# MSGP.net
KiCad netlist of a schematic drawn in EAGLE
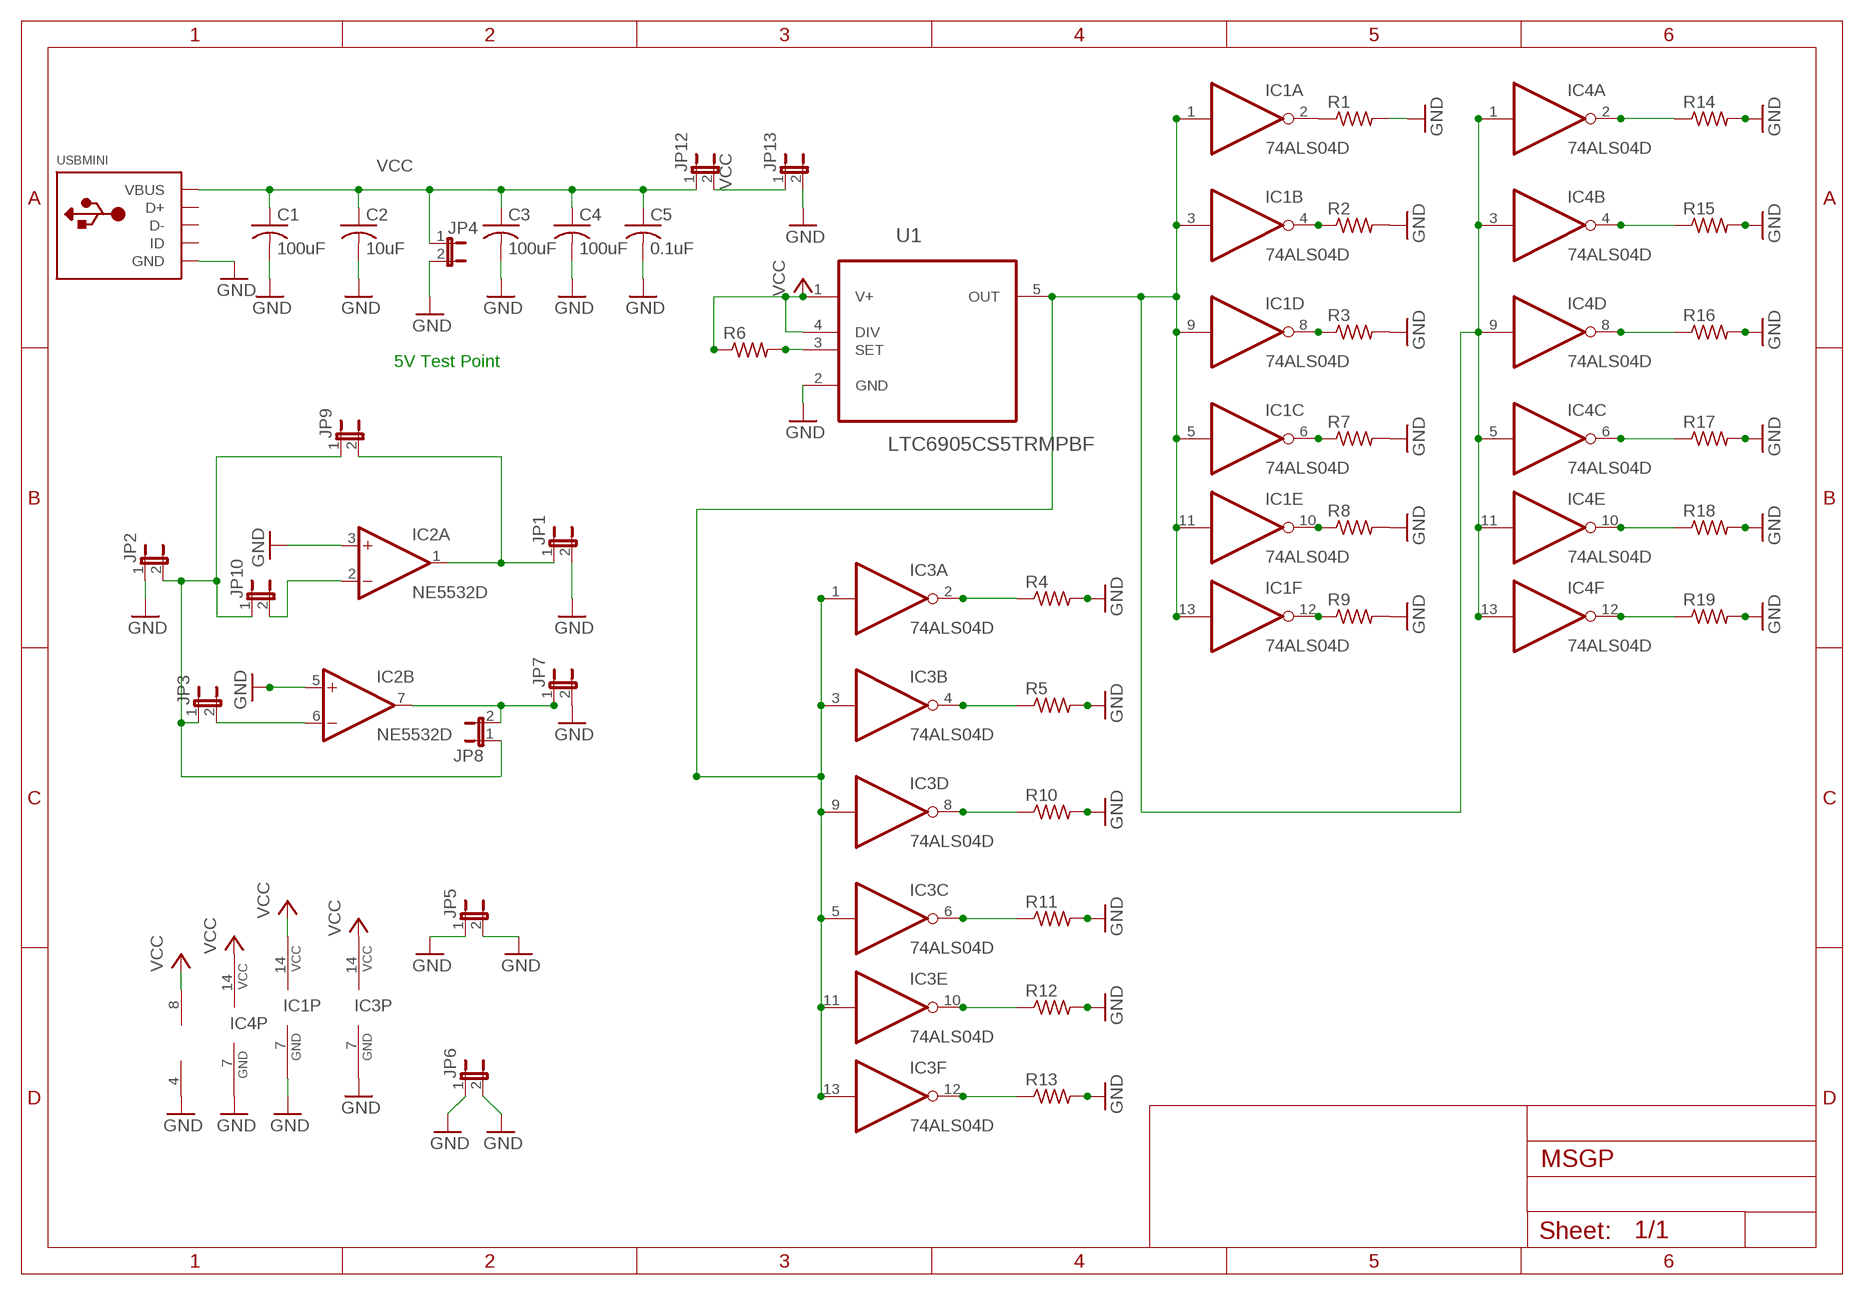
[diagram p0: schematic, sheet 1]

(export (version "E")
  (design (tool "Eeschema 10.0.6"))
  (components
    (comp (ref "C1")
      (value "100uF")
      (footprint "eagle-import:C1206K")
      (libsource (lib "eagle-import") (part "C-USC1206K"))
    )
    (comp (ref "C2")
      (value "10uF")
      (footprint "eagle-import:C1206K")
      (libsource (lib "eagle-import") (part "C-USC1206K"))
    )
    (comp (ref "C3")
      (value "100uF")
      (footprint "eagle-import:C1206K")
      (libsource (lib "eagle-import") (part "C-USC1206K"))
    )
    (comp (ref "C4")
      (value "100uF")
      (footprint "eagle-import:C1206K")
      (libsource (lib "eagle-import") (part "C-USC1206K"))
    )
    (comp (ref "C5")
      (value "0.1uF")
      (footprint "eagle-import:C1206K")
      (libsource (lib "eagle-import") (part "C-USC1206K"))
    )
    (comp (ref "IC1")
      (value "74ALS04D")
      (footprint "eagle-import:SO14")
      (libsource (lib "eagle-import") (part "7404DALS"))
    )
    (comp (ref "IC2")
      (value "NE5532D")
      (footprint "eagle-import:SO08")
      (libsource (lib "eagle-import") (part "NE5532D"))
    )
    (comp (ref "IC3")
      (value "74ALS04D")
      (footprint "eagle-import:SO14")
      (libsource (lib "eagle-import") (part "7404DALS"))
    )
    (comp (ref "IC4")
      (value "74ALS04D")
      (footprint "eagle-import:SO14")
      (libsource (lib "eagle-import") (part "7404DALS"))
    )
    (comp (ref "JP1")
      (value "JP1E")
      (footprint "eagle-import:JP1")
      (libsource (lib "eagle-import") (part "JP1E"))
    )
    (comp (ref "JP2")
      (value "JP1E")
      (footprint "eagle-import:JP1")
      (libsource (lib "eagle-import") (part "JP1E"))
    )
    (comp (ref "JP3")
      (value "JP1E")
      (footprint "eagle-import:JP1")
      (libsource (lib "eagle-import") (part "JP1E"))
    )
    (comp (ref "JP4")
      (value "JP1E")
      (footprint "eagle-import:JP1")
      (libsource (lib "eagle-import") (part "JP1E"))
    )
    (comp (ref "JP5")
      (value "JP1E")
      (footprint "eagle-import:JP1")
      (libsource (lib "eagle-import") (part "JP1E"))
    )
    (comp (ref "JP6")
      (value "JP1E")
      (footprint "eagle-import:JP1")
      (libsource (lib "eagle-import") (part "JP1E"))
    )
    (comp (ref "JP7")
      (value "JP1E")
      (footprint "eagle-import:JP1")
      (libsource (lib "eagle-import") (part "JP1E"))
    )
    (comp (ref "JP8")
      (value "JP1E")
      (footprint "eagle-import:JP1")
      (libsource (lib "eagle-import") (part "JP1E"))
    )
    (comp (ref "JP9")
      (value "JP1E")
      (footprint "eagle-import:JP1")
      (libsource (lib "eagle-import") (part "JP1E"))
    )
    (comp (ref "JP10")
      (value "JP1E")
      (footprint "eagle-import:JP1")
      (libsource (lib "eagle-import") (part "JP1E"))
    )
    (comp (ref "JP12")
      (value "JP1E")
      (footprint "eagle-import:JP1")
      (libsource (lib "eagle-import") (part "JP1E"))
    )
    (comp (ref "JP13")
      (value "JP1E")
      (footprint "eagle-import:JP1")
      (libsource (lib "eagle-import") (part "JP1E"))
    )
    (comp (ref "R1")
      (value "R-US_0204/2V")
      (footprint "eagle-import:0204V")
      (libsource (lib "eagle-import") (part "R-US_0204/2V"))
    )
    (comp (ref "R2")
      (value "R-US_0204/2V")
      (footprint "eagle-import:0204V")
      (libsource (lib "eagle-import") (part "R-US_0204/2V"))
    )
    (comp (ref "R3")
      (value "R-US_0204/2V")
      (footprint "eagle-import:0204V")
      (libsource (lib "eagle-import") (part "R-US_0204/2V"))
    )
    (comp (ref "R4")
      (value "R-US_0204/2V")
      (footprint "eagle-import:0204V")
      (libsource (lib "eagle-import") (part "R-US_0204/2V"))
    )
    (comp (ref "R5")
      (value "R-US_0204/2V")
      (footprint "eagle-import:0204V")
      (libsource (lib "eagle-import") (part "R-US_0204/2V"))
    )
    (comp (ref "R6")
      (value "R-US_0204/2V")
      (footprint "eagle-import:0204V")
      (libsource (lib "eagle-import") (part "R-US_0204/2V"))
    )
    (comp (ref "R7")
      (value "R-US_0204/2V")
      (footprint "eagle-import:0204V")
      (libsource (lib "eagle-import") (part "R-US_0204/2V"))
    )
    (comp (ref "R8")
      (value "R-US_0204/2V")
      (footprint "eagle-import:0204V")
      (libsource (lib "eagle-import") (part "R-US_0204/2V"))
    )
    (comp (ref "R9")
      (value "R-US_0204/2V")
      (footprint "eagle-import:0204V")
      (libsource (lib "eagle-import") (part "R-US_0204/2V"))
    )
    (comp (ref "R10")
      (value "R-US_0204/2V")
      (footprint "eagle-import:0204V")
      (libsource (lib "eagle-import") (part "R-US_0204/2V"))
    )
    (comp (ref "R11")
      (value "R-US_0204/2V")
      (footprint "eagle-import:0204V")
      (libsource (lib "eagle-import") (part "R-US_0204/2V"))
    )
    (comp (ref "R12")
      (value "R-US_0204/2V")
      (footprint "eagle-import:0204V")
      (libsource (lib "eagle-import") (part "R-US_0204/2V"))
    )
    (comp (ref "R13")
      (value "R-US_0204/2V")
      (footprint "eagle-import:0204V")
      (libsource (lib "eagle-import") (part "R-US_0204/2V"))
    )
    (comp (ref "R14")
      (value "R-US_0204/2V")
      (footprint "eagle-import:0204V")
      (libsource (lib "eagle-import") (part "R-US_0204/2V"))
    )
    (comp (ref "R15")
      (value "R-US_0204/2V")
      (footprint "eagle-import:0204V")
      (libsource (lib "eagle-import") (part "R-US_0204/2V"))
    )
    (comp (ref "R16")
      (value "R-US_0204/2V")
      (footprint "eagle-import:0204V")
      (libsource (lib "eagle-import") (part "R-US_0204/2V"))
    )
    (comp (ref "R17")
      (value "R-US_0204/2V")
      (footprint "eagle-import:0204V")
      (libsource (lib "eagle-import") (part "R-US_0204/2V"))
    )
    (comp (ref "R18")
      (value "R-US_0204/2V")
      (footprint "eagle-import:0204V")
      (libsource (lib "eagle-import") (part "R-US_0204/2V"))
    )
    (comp (ref "R19")
      (value "R-US_0204/2V")
      (footprint "eagle-import:0204V")
      (libsource (lib "eagle-import") (part "R-US_0204/2V"))
    )
    (comp (ref "U1")
      (value "LTC6905CS5TRMPBF")
      (footprint "eagle-import:SOT95P280X100-5N")
      (fields (field (name "MPN") "LTC6905CS5#TRMPBF"))
      (libsource (lib "eagle-import") (part "LTC6905CS5TRMPBF"))
    )
    (comp (ref "USBMINI")
      (value "USBMINIB")
      (footprint "eagle-import:USB-MINIB")
      (libsource (lib "eagle-import") (part "USBMINIB"))
    )
  )
  (nets
    (net (code "1") (name "GND") (class "Default")
      (node (ref "C1") (pin "2") (pinfunction "2_2") (pintype "passive"))
      (node (ref "C2") (pin "2") (pinfunction "2_2") (pintype "passive"))
      (node (ref "C3") (pin "2") (pinfunction "2_2") (pintype "passive"))
      (node (ref "C4") (pin "2") (pinfunction "2_2") (pintype "passive"))
      (node (ref "C5") (pin "2") (pinfunction "2_2") (pintype "passive"))
      (node (ref "IC1") (pin "7") (pinfunction "GND_7") (pintype "power_in"))
      (node (ref "IC2") (pin "3") (pinfunction "+IN_3") (pintype "input"))
      (node (ref "IC2") (pin "4") (pinfunction "V-_4") (pintype "power_in"))
      (node (ref "IC2") (pin "5") (pinfunction "+IN_5") (pintype "input"))
      (node (ref "IC3") (pin "7") (pinfunction "GND_7") (pintype "power_in"))
      (node (ref "IC4") (pin "7") (pinfunction "GND_7") (pintype "power_in"))
      (node (ref "JP1") (pin "2") (pinfunction "2_2") (pintype "passive"))
      (node (ref "JP13") (pin "2") (pinfunction "2_2") (pintype "passive"))
      (node (ref "JP2") (pin "1") (pinfunction "1_1") (pintype "passive"))
      (node (ref "JP4") (pin "2") (pinfunction "2_2") (pintype "passive"))
      (node (ref "JP5") (pin "1") (pinfunction "1_1") (pintype "passive"))
      (node (ref "JP5") (pin "2") (pinfunction "2_2") (pintype "passive"))
      (node (ref "JP6") (pin "1") (pinfunction "1_1") (pintype "passive"))
      (node (ref "JP6") (pin "2") (pinfunction "2_2") (pintype "passive"))
      (node (ref "JP7") (pin "2") (pinfunction "2_2") (pintype "passive"))
      (node (ref "R1") (pin "2") (pinfunction "2_2") (pintype "passive"))
      (node (ref "R10") (pin "2") (pinfunction "2_2") (pintype "passive"))
      (node (ref "R11") (pin "2") (pinfunction "2_2") (pintype "passive"))
      (node (ref "R12") (pin "2") (pinfunction "2_2") (pintype "passive"))
      (node (ref "R13") (pin "2") (pinfunction "2_2") (pintype "passive"))
      (node (ref "R14") (pin "2") (pinfunction "2_2") (pintype "passive"))
      (node (ref "R15") (pin "2") (pinfunction "2_2") (pintype "passive"))
      (node (ref "R16") (pin "2") (pinfunction "2_2") (pintype "passive"))
      (node (ref "R17") (pin "2") (pinfunction "2_2") (pintype "passive"))
      (node (ref "R18") (pin "2") (pinfunction "2_2") (pintype "passive"))
      (node (ref "R19") (pin "2") (pinfunction "2_2") (pintype "passive"))
      (node (ref "R2") (pin "2") (pinfunction "2_2") (pintype "passive"))
      (node (ref "R3") (pin "2") (pinfunction "2_2") (pintype "passive"))
      (node (ref "R4") (pin "2") (pinfunction "2_2") (pintype "passive"))
      (node (ref "R5") (pin "2") (pinfunction "2_2") (pintype "passive"))
      (node (ref "R7") (pin "2") (pinfunction "2_2") (pintype "passive"))
      (node (ref "R8") (pin "2") (pinfunction "2_2") (pintype "passive"))
      (node (ref "R9") (pin "2") (pinfunction "2_2") (pintype "passive"))
      (node (ref "U1") (pin "2") (pinfunction "GND_2") (pintype "passive"))
      (node (ref "USBMINI") (pin "GND") (pinfunction "GND_GND") (pintype "power_in"))
    )
    (net (code "2") (name "Net-(IC1A-I)") (class "Default")
      (node (ref "IC1") (pin "1") (pinfunction "I_1") (pintype "input"))
      (node (ref "IC1") (pin "11") (pinfunction "I_11") (pintype "input"))
      (node (ref "IC1") (pin "13") (pinfunction "I_13") (pintype "input"))
      (node (ref "IC1") (pin "3") (pinfunction "I_3") (pintype "input"))
      (node (ref "IC1") (pin "5") (pinfunction "I_5") (pintype "input"))
      (node (ref "IC1") (pin "9") (pinfunction "I_9") (pintype "input"))
      (node (ref "IC3") (pin "1") (pinfunction "I_1") (pintype "input"))
      (node (ref "IC3") (pin "11") (pinfunction "I_11") (pintype "input"))
      (node (ref "IC3") (pin "13") (pinfunction "I_13") (pintype "input"))
      (node (ref "IC3") (pin "3") (pinfunction "I_3") (pintype "input"))
      (node (ref "IC3") (pin "5") (pinfunction "I_5") (pintype "input"))
      (node (ref "IC3") (pin "9") (pinfunction "I_9") (pintype "input"))
      (node (ref "IC4") (pin "1") (pinfunction "I_1") (pintype "input"))
      (node (ref "IC4") (pin "11") (pinfunction "I_11") (pintype "input"))
      (node (ref "IC4") (pin "13") (pinfunction "I_13") (pintype "input"))
      (node (ref "IC4") (pin "3") (pinfunction "I_3") (pintype "input"))
      (node (ref "IC4") (pin "5") (pinfunction "I_5") (pintype "input"))
      (node (ref "IC4") (pin "9") (pinfunction "I_9") (pintype "input"))
      (node (ref "U1") (pin "5") (pinfunction "OUT_5") (pintype "output"))
    )
    (net (code "3") (name "Net-(IC1A-O)") (class "Default")
      (node (ref "IC1") (pin "2") (pinfunction "O_2") (pintype "output"))
      (node (ref "R1") (pin "1") (pinfunction "1_1") (pintype "passive"))
    )
    (net (code "4") (name "Net-(IC1B-O)") (class "Default")
      (node (ref "IC1") (pin "4") (pinfunction "O_4") (pintype "output"))
      (node (ref "R2") (pin "1") (pinfunction "1_1") (pintype "passive"))
    )
    (net (code "5") (name "Net-(IC1C-O)") (class "Default")
      (node (ref "IC1") (pin "6") (pinfunction "O_6") (pintype "output"))
      (node (ref "R7") (pin "1") (pinfunction "1_1") (pintype "passive"))
    )
    (net (code "6") (name "Net-(IC1D-O)") (class "Default")
      (node (ref "IC1") (pin "8") (pinfunction "O_8") (pintype "output"))
      (node (ref "R3") (pin "1") (pinfunction "1_1") (pintype "passive"))
    )
    (net (code "7") (name "Net-(IC1E-O)") (class "Default")
      (node (ref "IC1") (pin "10") (pinfunction "O_10") (pintype "output"))
      (node (ref "R8") (pin "1") (pinfunction "1_1") (pintype "passive"))
    )
    (net (code "8") (name "Net-(IC1F-O)") (class "Default")
      (node (ref "IC1") (pin "12") (pinfunction "O_12") (pintype "output"))
      (node (ref "R9") (pin "1") (pinfunction "1_1") (pintype "passive"))
    )
    (net (code "9") (name "Net-(IC2A--IN)") (class "Default")
      (node (ref "IC2") (pin "2") (pinfunction "-IN_2") (pintype "input"))
      (node (ref "JP10") (pin "2") (pinfunction "2_2") (pintype "passive"))
    )
    (net (code "10") (name "Net-(IC2A-OUT)") (class "Default")
      (node (ref "IC2") (pin "1") (pinfunction "OUT_1") (pintype "output"))
      (node (ref "JP1") (pin "1") (pinfunction "1_1") (pintype "passive"))
      (node (ref "JP9") (pin "2") (pinfunction "2_2") (pintype "passive"))
    )
    (net (code "11") (name "Net-(IC2B--IN)") (class "Default")
      (node (ref "IC2") (pin "6") (pinfunction "-IN_6") (pintype "input"))
      (node (ref "JP3") (pin "2") (pinfunction "2_2") (pintype "passive"))
    )
    (net (code "12") (name "Net-(IC2B-OUT)") (class "Default")
      (node (ref "IC2") (pin "7") (pinfunction "OUT_7") (pintype "output"))
      (node (ref "JP7") (pin "1") (pinfunction "1_1") (pintype "passive"))
      (node (ref "JP8") (pin "2") (pinfunction "2_2") (pintype "passive"))
    )
    (net (code "13") (name "Net-(IC3A-O)") (class "Default")
      (node (ref "IC3") (pin "2") (pinfunction "O_2") (pintype "output"))
      (node (ref "R4") (pin "1") (pinfunction "1_1") (pintype "passive"))
    )
    (net (code "14") (name "Net-(IC3B-O)") (class "Default")
      (node (ref "IC3") (pin "4") (pinfunction "O_4") (pintype "output"))
      (node (ref "R5") (pin "1") (pinfunction "1_1") (pintype "passive"))
    )
    (net (code "15") (name "Net-(IC3C-O)") (class "Default")
      (node (ref "IC3") (pin "6") (pinfunction "O_6") (pintype "output"))
      (node (ref "R11") (pin "1") (pinfunction "1_1") (pintype "passive"))
    )
    (net (code "16") (name "Net-(IC3D-O)") (class "Default")
      (node (ref "IC3") (pin "8") (pinfunction "O_8") (pintype "output"))
      (node (ref "R10") (pin "1") (pinfunction "1_1") (pintype "passive"))
    )
    (net (code "17") (name "Net-(IC3E-O)") (class "Default")
      (node (ref "IC3") (pin "10") (pinfunction "O_10") (pintype "output"))
      (node (ref "R12") (pin "1") (pinfunction "1_1") (pintype "passive"))
    )
    (net (code "18") (name "Net-(IC3F-O)") (class "Default")
      (node (ref "IC3") (pin "12") (pinfunction "O_12") (pintype "output"))
      (node (ref "R13") (pin "1") (pinfunction "1_1") (pintype "passive"))
    )
    (net (code "19") (name "Net-(IC4A-O)") (class "Default")
      (node (ref "IC4") (pin "2") (pinfunction "O_2") (pintype "output"))
      (node (ref "R14") (pin "1") (pinfunction "1_1") (pintype "passive"))
    )
    (net (code "20") (name "Net-(IC4B-O)") (class "Default")
      (node (ref "IC4") (pin "4") (pinfunction "O_4") (pintype "output"))
      (node (ref "R15") (pin "1") (pinfunction "1_1") (pintype "passive"))
    )
    (net (code "21") (name "Net-(IC4C-O)") (class "Default")
      (node (ref "IC4") (pin "6") (pinfunction "O_6") (pintype "output"))
      (node (ref "R17") (pin "1") (pinfunction "1_1") (pintype "passive"))
    )
    (net (code "22") (name "Net-(IC4D-O)") (class "Default")
      (node (ref "IC4") (pin "8") (pinfunction "O_8") (pintype "output"))
      (node (ref "R16") (pin "1") (pinfunction "1_1") (pintype "passive"))
    )
    (net (code "23") (name "Net-(IC4E-O)") (class "Default")
      (node (ref "IC4") (pin "10") (pinfunction "O_10") (pintype "output"))
      (node (ref "R18") (pin "1") (pinfunction "1_1") (pintype "passive"))
    )
    (net (code "24") (name "Net-(IC4F-O)") (class "Default")
      (node (ref "IC4") (pin "12") (pinfunction "O_12") (pintype "output"))
      (node (ref "R19") (pin "1") (pinfunction "1_1") (pintype "passive"))
    )
    (net (code "25") (name "Net-(JP10-Pad1)") (class "Default")
      (node (ref "JP10") (pin "1") (pinfunction "1_1") (pintype "passive"))
      (node (ref "JP2") (pin "2") (pinfunction "2_2") (pintype "passive"))
      (node (ref "JP3") (pin "1") (pinfunction "1_1") (pintype "passive"))
      (node (ref "JP8") (pin "1") (pinfunction "1_1") (pintype "passive"))
      (node (ref "JP9") (pin "1") (pinfunction "1_1") (pintype "passive"))
    )
    (net (code "26") (name "Net-(U1-SET)") (class "Default")
      (node (ref "R6") (pin "2") (pinfunction "2_2") (pintype "passive"))
      (node (ref "U1") (pin "3") (pinfunction "SET_3") (pintype "input"))
    )
    (net (code "27") (name "VCC") (class "Default")
      (node (ref "C1") (pin "1") (pinfunction "1_1") (pintype "passive"))
      (node (ref "C2") (pin "1") (pinfunction "1_1") (pintype "passive"))
      (node (ref "C3") (pin "1") (pinfunction "1_1") (pintype "passive"))
      (node (ref "C4") (pin "1") (pinfunction "1_1") (pintype "passive"))
      (node (ref "C5") (pin "1") (pinfunction "1_1") (pintype "passive"))
      (node (ref "IC1") (pin "14") (pinfunction "VCC_14") (pintype "power_in"))
      (node (ref "IC2") (pin "8") (pinfunction "V+_8") (pintype "power_in"))
      (node (ref "IC3") (pin "14") (pinfunction "VCC_14") (pintype "power_in"))
      (node (ref "IC4") (pin "14") (pinfunction "VCC_14") (pintype "power_in"))
      (node (ref "JP12") (pin "1") (pinfunction "1_1") (pintype "passive"))
      (node (ref "JP12") (pin "2") (pinfunction "2_2") (pintype "passive"))
      (node (ref "JP13") (pin "1") (pinfunction "1_1") (pintype "passive"))
      (node (ref "JP4") (pin "1") (pinfunction "1_1") (pintype "passive"))
      (node (ref "R6") (pin "1") (pinfunction "1_1") (pintype "passive"))
      (node (ref "U1") (pin "1") (pinfunction "V+_1") (pintype "power_in"))
      (node (ref "U1") (pin "4") (pinfunction "DIV_4") (pintype "input"))
      (node (ref "USBMINI") (pin "VBUS") (pinfunction "VBUS_VBUS") (pintype "power_in"))
    )
    (net (code "28") (name "unconnected-(USBMINI-PadD+)") (class "Default")
      (node (ref "USBMINI") (pin "D+") (pinfunction "D+_D+") (pintype "bidirectional"))
    )
    (net (code "29") (name "unconnected-(USBMINI-PadD-)") (class "Default")
      (node (ref "USBMINI") (pin "D-") (pinfunction "D-_D-") (pintype "bidirectional"))
    )
    (net (code "30") (name "unconnected-(USBMINI-PadID)") (class "Default")
      (node (ref "USBMINI") (pin "ID") (pinfunction "ID_ID") (pintype "bidirectional"))
    )
  )
)
